# Curtch_Sheet.net
KiCad netlist of a schematic drawn in Altium Designer
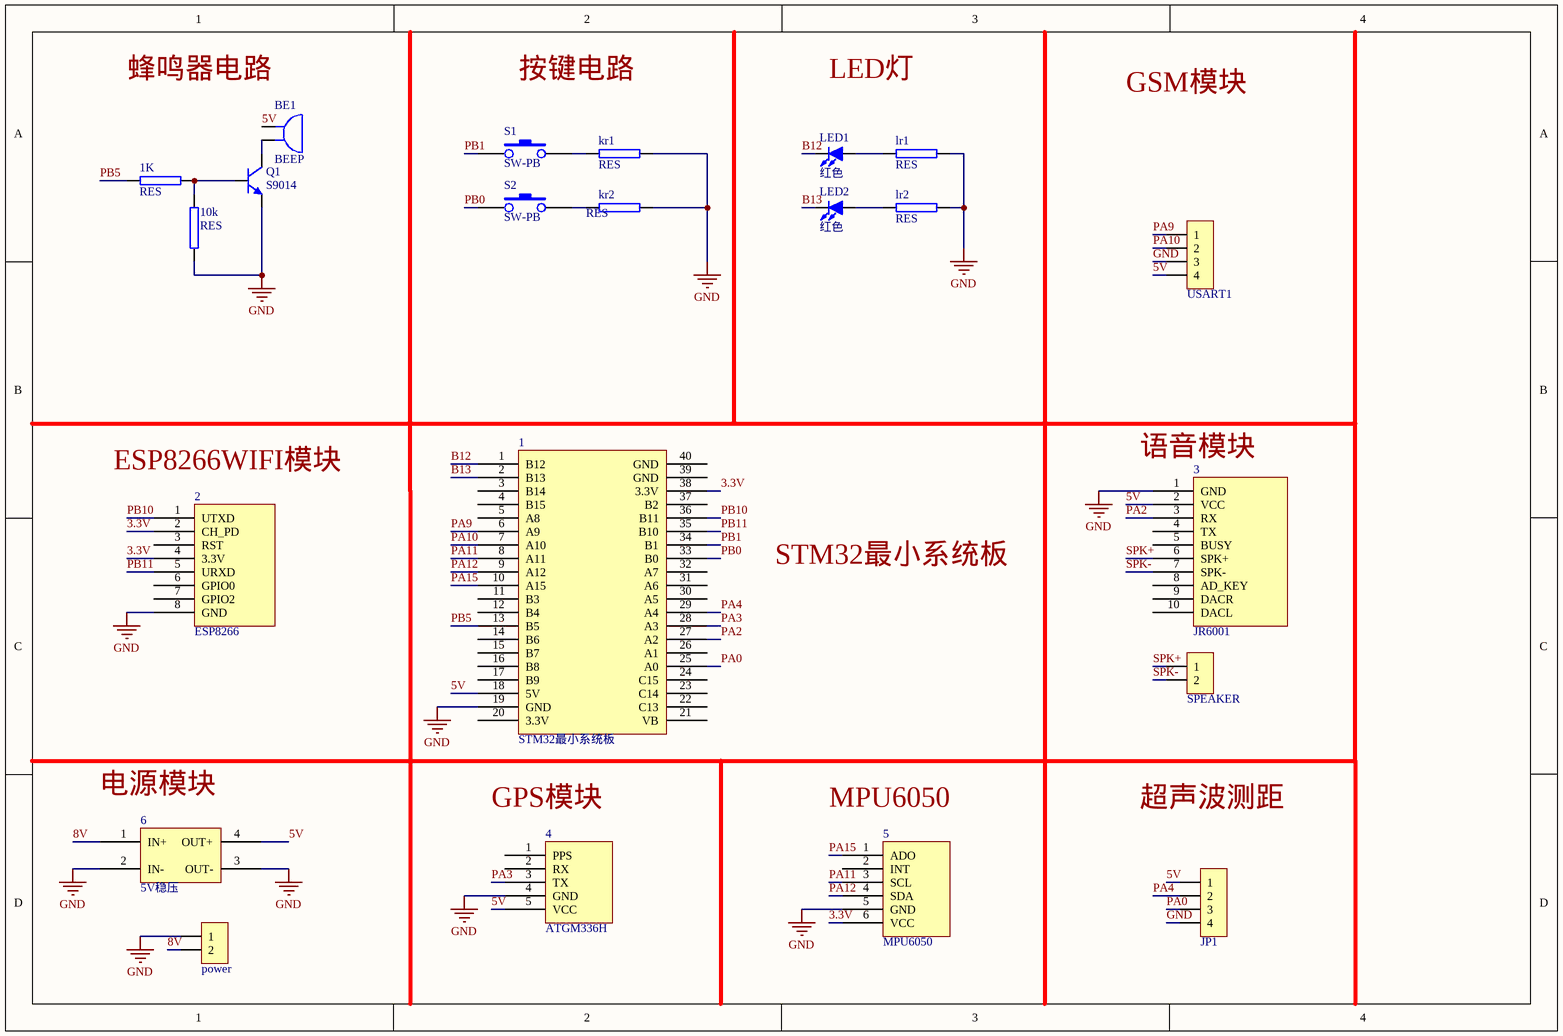
[diagram p0: Curtch_Sheet.SchDoc]

(export (version "E")
  (design (tool "Eeschema 10.0.6"))
  (components
    (comp (ref "1")
      (value "STM32最小系统板")
      (footprint "DIP40")
      (libsource (lib "STM32最小系统板") (part "STM32最小系统板"))
    )
    (comp (ref "1K") (value "RES") (footprint "AXIAL0.4") (libsource (lib "常用元件库") (part "RES")))
    (comp (ref "2")
      (value "ESP8266")
      (footprint "DIP8 - duplicate")
      (libsource (lib "ESP8266") (part "Component_1"))
    )
    (comp (ref "3") (value "JR6001") (footprint "DIP20") (libsource (lib "JR6001") (part "JR6001")))
    (comp (ref "4") (value "ATGM336H") (footprint "DIP10") (libsource (lib "ATGM336H") (part "ATGM336H")))
    (comp (ref "5") (value "MPU6050") (footprint "MPU6050") (libsource (lib "MPU6050") (part "MPU6050")))
    (comp (ref "6") (value "5V稳压") (footprint "DIP16") (libsource (lib "5V稳压") (part "5V稳压")))
    (comp (ref "10k") (value "RES") (footprint "AXIAL0.4") (libsource (lib "常用元件库") (part "RES")))
    (comp (ref "BE1") (value "BEEP") (footprint "BEEP 7.6x12x7.5") (libsource (lib "F蜂鸣器") (part "BEEP")))
    (comp (ref "JP1")
      (value "HDR-1X4")
      (footprint "HDR2.54-LI-4P")
      (description "4P接插件")
      (fields (field (name "版权归属") "源创客"))
      (libsource (lib "4.5   - 接插件-脚距2.54") (part "Header 4"))
    )
    (comp (ref "kr1") (value "RES") (footprint "AXIAL0.4") (libsource (lib "常用元件库") (part "RES")))
    (comp (ref "kr2") (value "RES") (footprint "AXIAL0.4") (libsource (lib "常用元件库") (part "RES")))
    (comp (ref "LED1")
      (value "红色")
      (footprint "LED 5MM-B")
      (description "5mm插件LED")
      (fields (field (name "版权归属") "源创客"))
      (libsource (lib "9.1   - LED") (part "LED-5MM"))
    )
    (comp (ref "LED2")
      (value "红色")
      (footprint "LED 5MM-B")
      (description "5mm插件LED")
      (fields (field (name "版权归属") "源创客"))
      (libsource (lib "9.1   - LED") (part "LED-5MM"))
    )
    (comp (ref "lr1") (value "RES") (footprint "AXIAL0.4") (libsource (lib "常用元件库") (part "RES")))
    (comp (ref "lr2") (value "RES") (footprint "AXIAL0.4") (libsource (lib "常用元件库") (part "RES")))
    (comp (ref "power")
      (value "HDR-1X2")
      (footprint "HDR2.54-Y-LI-2P")
      (description "2P接插件")
      (fields (field (name "版权归属") "源创客"))
      (libsource (lib "4.5   - 接插件-脚距2.54") (part "Header 2"))
    )
    (comp (ref "Q1")
      (value "S9014")
      (footprint "TO92A")
      (description "低噪放大-NPN型")
      (fields (field (name "版权归属") "源创客"))
      (libsource (lib "6.2   - 三极管") (part "9014-DIP"))
    )
    (comp (ref "S1") (value "SW-PB") (footprint "SW6*6") (libsource (lib "第三期元件") (part "SW-PB")))
    (comp (ref "S2") (value "SW-PB") (footprint "SW6*6") (libsource (lib "第三期元件") (part "SW-PB")))
    (comp (ref "SPEAKER")
      (value "HDR-1X2")
      (footprint "HDR2.54-Y-LI-2P")
      (description "2P接插件")
      (fields (field (name "版权归属") "源创客"))
      (libsource (lib "4.5   - 接插件-脚距2.54") (part "Header 2"))
    )
    (comp (ref "USART1")
      (value "HDR-1X4")
      (footprint "HDR2.54-Y-LI-4P")
      (description "4P接插件")
      (fields (field (name "版权归属") "源创客"))
      (libsource (lib "4.5   - 接插件-脚距2.54") (part "Header 4"))
    )
  )
  (nets
    (net (code "1") (name "/3.3V") (class "Default")
      (node (ref "1") (pin "38") (pinfunction "3.3V_38") (pintype "passive"))
      (node (ref "2") (pin "2") (pinfunction "CH_PD_2") (pintype "passive"))
      (node (ref "2") (pin "4") (pinfunction "3.3V_4") (pintype "passive"))
      (node (ref "5") (pin "6") (pinfunction "VCC_6") (pintype "passive"))
    )
    (net (code "2") (name "/5V") (class "Default")
      (node (ref "1") (pin "18") (pinfunction "5V_18") (pintype "passive"))
      (node (ref "3") (pin "2") (pinfunction "VCC_2") (pintype "passive"))
      (node (ref "4") (pin "5") (pinfunction "VCC_5") (pintype "passive"))
      (node (ref "6") (pin "4") (pinfunction "OUT+_4") (pintype "passive"))
      (node (ref "BE1") (pin "1") (pintype "passive"))
      (node (ref "JP1") (pin "1") (pinfunction "1_1") (pintype "passive"))
      (node (ref "USART1") (pin "4") (pinfunction "4_4") (pintype "passive"))
    )
    (net (code "3") (name "/8V") (class "Default")
      (node (ref "6") (pin "1") (pinfunction "IN+_1") (pintype "passive"))
      (node (ref "power") (pin "2") (pinfunction "2_2") (pintype "passive"))
    )
    (net (code "4") (name "/B12") (class "Default")
      (node (ref "1") (pin "1") (pinfunction "B12_1") (pintype "passive"))
      (node (ref "LED1") (pin "2") (pinfunction "K_2") (pintype "passive"))
    )
    (net (code "5") (name "/B13") (class "Default")
      (node (ref "1") (pin "2") (pinfunction "B13_2") (pintype "passive"))
      (node (ref "LED2") (pin "2") (pinfunction "K_2") (pintype "passive"))
    )
    (net (code "6") (name "/PA0") (class "Default")
      (node (ref "1") (pin "25") (pinfunction "A0_25") (pintype "passive"))
      (node (ref "JP1") (pin "3") (pinfunction "3_3") (pintype "passive"))
    )
    (net (code "7") (name "/PA2") (class "Default")
      (node (ref "1") (pin "27") (pinfunction "A2_27") (pintype "passive"))
      (node (ref "3") (pin "3") (pinfunction "RX_3") (pintype "passive"))
    )
    (net (code "8") (name "/PA3") (class "Default")
      (node (ref "1") (pin "28") (pinfunction "A3_28") (pintype "passive"))
      (node (ref "4") (pin "3") (pinfunction "TX_3") (pintype "passive"))
    )
    (net (code "9") (name "/PA4") (class "Default")
      (node (ref "1") (pin "29") (pinfunction "A4_29") (pintype "passive"))
      (node (ref "JP1") (pin "2") (pinfunction "2_2") (pintype "passive"))
    )
    (net (code "10") (name "/PA9") (class "Default")
      (node (ref "1") (pin "6") (pinfunction "A9_6") (pintype "passive"))
      (node (ref "USART1") (pin "1") (pinfunction "1_1") (pintype "passive"))
    )
    (net (code "11") (name "/PA10") (class "Default")
      (node (ref "1") (pin "7") (pinfunction "A10_7") (pintype "passive"))
      (node (ref "USART1") (pin "2") (pinfunction "2_2") (pintype "passive"))
    )
    (net (code "12") (name "/PA11") (class "Default")
      (node (ref "1") (pin "8") (pinfunction "A11_8") (pintype "passive"))
      (node (ref "5") (pin "3") (pinfunction "SCL_3") (pintype "passive"))
    )
    (net (code "13") (name "/PA12") (class "Default")
      (node (ref "1") (pin "9") (pinfunction "A12_9") (pintype "passive"))
      (node (ref "5") (pin "4") (pinfunction "SDA_4") (pintype "passive"))
    )
    (net (code "14") (name "/PA15") (class "Default")
      (node (ref "1") (pin "10") (pinfunction "A15_10") (pintype "passive"))
      (node (ref "5") (pin "1") (pinfunction "ADO_1") (pintype "passive"))
    )
    (net (code "15") (name "/PB0") (class "Default")
      (node (ref "1") (pin "33") (pinfunction "B0_33") (pintype "passive"))
      (node (ref "S2") (pin "1") (pinfunction "1_1") (pintype "passive"))
    )
    (net (code "16") (name "/PB1") (class "Default")
      (node (ref "1") (pin "34") (pinfunction "B1_34") (pintype "passive"))
      (node (ref "S1") (pin "1") (pinfunction "1_1") (pintype "passive"))
    )
    (net (code "17") (name "/PB5") (class "Default")
      (node (ref "1") (pin "13") (pinfunction "B5_13") (pintype "passive"))
      (node (ref "1K") (pin "1") (pinfunction "1_1") (pintype "passive"))
    )
    (net (code "18") (name "/PB10") (class "Default")
      (node (ref "1") (pin "36") (pinfunction "B11_36") (pintype "passive"))
      (node (ref "2") (pin "1") (pinfunction "UTXD_1") (pintype "passive"))
    )
    (net (code "19") (name "/PB11") (class "Default")
      (node (ref "1") (pin "35") (pinfunction "B10_35") (pintype "passive"))
      (node (ref "2") (pin "5") (pinfunction "URXD_5") (pintype "passive"))
    )
    (net (code "20") (name "/SPK+") (class "Default")
      (node (ref "3") (pin "6") (pinfunction "SPK+_6") (pintype "passive"))
      (node (ref "SPEAKER") (pin "1") (pinfunction "1_1") (pintype "passive"))
    )
    (net (code "21") (name "/SPK-") (class "Default")
      (node (ref "3") (pin "7") (pinfunction "SPK-_7") (pintype "passive"))
      (node (ref "SPEAKER") (pin "2") (pinfunction "2_2") (pintype "passive"))
    )
    (net (code "22") (name "GND") (class "Default")
      (node (ref "1") (pin "19") (pinfunction "GND_19") (pintype "passive"))
      (node (ref "10k") (pin "2") (pinfunction "2_2") (pintype "passive"))
      (node (ref "2") (pin "8") (pinfunction "GND_8") (pintype "passive"))
      (node (ref "3") (pin "1") (pinfunction "GND_1") (pintype "passive"))
      (node (ref "4") (pin "4") (pinfunction "GND_4") (pintype "passive"))
      (node (ref "5") (pin "5") (pinfunction "GND_5") (pintype "passive"))
      (node (ref "6") (pin "2") (pinfunction "IN-_2") (pintype "passive"))
      (node (ref "6") (pin "3") (pinfunction "OUT-_3") (pintype "passive"))
      (node (ref "JP1") (pin "4") (pinfunction "4_4") (pintype "passive"))
      (node (ref "Q1") (pin "1") (pinfunction "E_1") (pintype "passive"))
      (node (ref "USART1") (pin "3") (pinfunction "3_3") (pintype "passive"))
      (node (ref "kr1") (pin "2") (pinfunction "2_2") (pintype "passive"))
      (node (ref "kr2") (pin "2") (pinfunction "2_2") (pintype "passive"))
      (node (ref "lr1") (pin "2") (pinfunction "2_2") (pintype "passive"))
      (node (ref "lr2") (pin "2") (pinfunction "2_2") (pintype "passive"))
      (node (ref "power") (pin "1") (pinfunction "1_1") (pintype "passive"))
    )
    (net (code "23") (name "Net-(LED1-A)") (class "Default")
      (node (ref "LED1") (pin "1") (pinfunction "A_1") (pintype "passive"))
      (node (ref "lr1") (pin "1") (pinfunction "1_1") (pintype "passive"))
    )
    (net (code "24") (name "Net-(LED2-A)") (class "Default")
      (node (ref "LED2") (pin "1") (pinfunction "A_1") (pintype "passive"))
      (node (ref "lr2") (pin "1") (pinfunction "1_1") (pintype "passive"))
    )
    (net (code "25") (name "Net-(Q1-B)") (class "Default")
      (node (ref "10k") (pin "1") (pinfunction "1_1") (pintype "passive"))
      (node (ref "1K") (pin "2") (pinfunction "2_2") (pintype "passive"))
      (node (ref "Q1") (pin "2") (pinfunction "B_2") (pintype "passive"))
    )
    (net (code "26") (name "Net-(Q1-C)") (class "Default")
      (node (ref "BE1") (pin "2") (pintype "passive"))
      (node (ref "Q1") (pin "3") (pinfunction "C_3") (pintype "passive"))
    )
    (net (code "27") (name "Net-(S1-Pad2)") (class "Default")
      (node (ref "S1") (pin "2") (pinfunction "2_2") (pintype "passive"))
      (node (ref "kr1") (pin "1") (pinfunction "1_1") (pintype "passive"))
    )
    (net (code "28") (name "Net-(S2-Pad2)") (class "Default")
      (node (ref "S2") (pin "2") (pinfunction "2_2") (pintype "passive"))
      (node (ref "kr2") (pin "1") (pinfunction "1_1") (pintype "passive"))
    )
    (net (code "29") (name "unconnected-(1-3.3V-Pad20)") (class "Default")
      (node (ref "1") (pin "20") (pinfunction "3.3V_20") (pintype "passive"))
    )
    (net (code "30") (name "unconnected-(1-A1-Pad26)") (class "Default")
      (node (ref "1") (pin "26") (pinfunction "A1_26") (pintype "passive"))
    )
    (net (code "31") (name "unconnected-(1-A5-Pad30)") (class "Default")
      (node (ref "1") (pin "30") (pinfunction "A5_30") (pintype "passive"))
    )
    (net (code "32") (name "unconnected-(1-A6-Pad31)") (class "Default")
      (node (ref "1") (pin "31") (pinfunction "A6_31") (pintype "passive"))
    )
    (net (code "33") (name "unconnected-(1-A7-Pad32)") (class "Default")
      (node (ref "1") (pin "32") (pinfunction "A7_32") (pintype "passive"))
    )
    (net (code "34") (name "unconnected-(1-A8-Pad5)") (class "Default")
      (node (ref "1") (pin "5") (pinfunction "A8_5") (pintype "passive"))
    )
    (net (code "35") (name "unconnected-(1-B2-Pad37)") (class "Default")
      (node (ref "1") (pin "37") (pinfunction "B2_37") (pintype "passive"))
    )
    (net (code "36") (name "unconnected-(1-B3-Pad11)") (class "Default")
      (node (ref "1") (pin "11") (pinfunction "B3_11") (pintype "passive"))
    )
    (net (code "37") (name "unconnected-(1-B4-Pad12)") (class "Default")
      (node (ref "1") (pin "12") (pinfunction "B4_12") (pintype "passive"))
    )
    (net (code "38") (name "unconnected-(1-B6-Pad14)") (class "Default")
      (node (ref "1") (pin "14") (pinfunction "B6_14") (pintype "passive"))
    )
    (net (code "39") (name "unconnected-(1-B7-Pad15)") (class "Default")
      (node (ref "1") (pin "15") (pinfunction "B7_15") (pintype "passive"))
    )
    (net (code "40") (name "unconnected-(1-B8-Pad16)") (class "Default")
      (node (ref "1") (pin "16") (pinfunction "B8_16") (pintype "passive"))
    )
    (net (code "41") (name "unconnected-(1-B9-Pad17)") (class "Default")
      (node (ref "1") (pin "17") (pinfunction "B9_17") (pintype "passive"))
    )
    (net (code "42") (name "unconnected-(1-B14-Pad3)") (class "Default")
      (node (ref "1") (pin "3") (pinfunction "B14_3") (pintype "passive"))
    )
    (net (code "43") (name "unconnected-(1-B15-Pad4)") (class "Default")
      (node (ref "1") (pin "4") (pinfunction "B15_4") (pintype "passive"))
    )
    (net (code "44") (name "unconnected-(1-C13-Pad22)") (class "Default")
      (node (ref "1") (pin "22") (pinfunction "C13_22") (pintype "passive"))
    )
    (net (code "45") (name "unconnected-(1-C14-Pad23)") (class "Default")
      (node (ref "1") (pin "23") (pinfunction "C14_23") (pintype "passive"))
    )
    (net (code "46") (name "unconnected-(1-C15-Pad24)") (class "Default")
      (node (ref "1") (pin "24") (pinfunction "C15_24") (pintype "passive"))
    )
    (net (code "47") (name "unconnected-(1-GND-Pad39)") (class "Default")
      (node (ref "1") (pin "39") (pinfunction "GND_39") (pintype "passive"))
    )
    (net (code "48") (name "unconnected-(1-GND-Pad40)") (class "Default")
      (node (ref "1") (pin "40") (pinfunction "GND_40") (pintype "passive"))
    )
    (net (code "49") (name "unconnected-(1-VB-Pad21)") (class "Default")
      (node (ref "1") (pin "21") (pinfunction "VB_21") (pintype "passive"))
    )
    (net (code "50") (name "unconnected-(2-GPIO0-Pad6)") (class "Default")
      (node (ref "2") (pin "6") (pinfunction "GPIO0_6") (pintype "passive"))
    )
    (net (code "51") (name "unconnected-(2-GPIO2-Pad7)") (class "Default")
      (node (ref "2") (pin "7") (pinfunction "GPIO2_7") (pintype "passive"))
    )
    (net (code "52") (name "unconnected-(2-RST-Pad3)") (class "Default")
      (node (ref "2") (pin "3") (pinfunction "RST_3") (pintype "passive"))
    )
    (net (code "53") (name "unconnected-(3-AD_KEY-Pad8)") (class "Default")
      (node (ref "3") (pin "8") (pinfunction "AD_KEY_8") (pintype "passive"))
    )
    (net (code "54") (name "unconnected-(3-BUSY-Pad5)") (class "Default")
      (node (ref "3") (pin "5") (pinfunction "BUSY_5") (pintype "passive"))
    )
    (net (code "55") (name "unconnected-(3-DACL-Pad10)") (class "Default")
      (node (ref "3") (pin "10") (pinfunction "DACL_10") (pintype "passive"))
    )
    (net (code "56") (name "unconnected-(3-DACR-Pad9)") (class "Default")
      (node (ref "3") (pin "9") (pinfunction "DACR_9") (pintype "passive"))
    )
    (net (code "57") (name "unconnected-(3-TX-Pad4)") (class "Default")
      (node (ref "3") (pin "4") (pinfunction "TX_4") (pintype "passive"))
    )
    (net (code "58") (name "unconnected-(4-PPS-Pad1)") (class "Default")
      (node (ref "4") (pin "1") (pinfunction "PPS_1") (pintype "passive"))
    )
    (net (code "59") (name "unconnected-(4-RX-Pad2)") (class "Default")
      (node (ref "4") (pin "2") (pinfunction "RX_2") (pintype "passive"))
    )
    (net (code "60") (name "unconnected-(5-INT-Pad2)") (class "Default")
      (node (ref "5") (pin "2") (pinfunction "INT_2") (pintype "passive"))
    )
  )
)
